# PCB-Switches.net
KiCad netlist of a schematic drawn in EAGLE
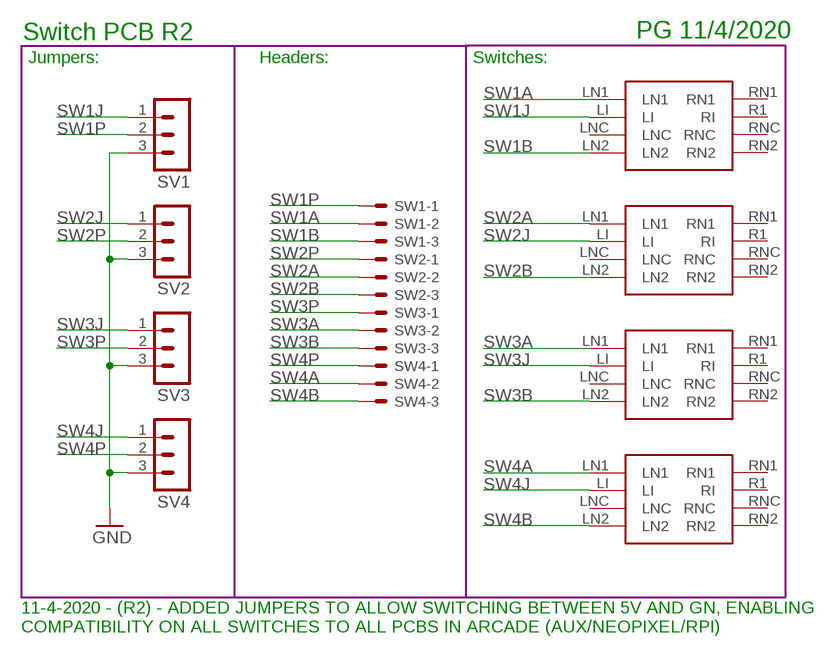
[diagram p0: schematic, sheet 1]

(export (version "E")
  (design (tool "Eeschema 10.0.6"))
  (components
    (comp (ref "SV1")
      (value "MA03-1")
      (footprint "eagle-import:MA03-1")
      (libsource (lib "eagle-import") (part "MA03-1"))
    )
    (comp (ref "SV2")
      (value "MA03-1")
      (footprint "eagle-import:MA03-1")
      (libsource (lib "eagle-import") (part "MA03-1"))
    )
    (comp (ref "SV3")
      (value "MA03-1")
      (footprint "eagle-import:MA03-1")
      (libsource (lib "eagle-import") (part "MA03-1"))
    )
    (comp (ref "SV4")
      (value "MA03-1")
      (footprint "eagle-import:MA03-1")
      (libsource (lib "eagle-import") (part "MA03-1"))
    )
    (comp (ref "SW1")
      (value "KK-156-3")
      (footprint "eagle-import:KK-156-3")
      (fields (field (name "MF") "MOLEX"))
      (libsource (lib "eagle-import") (part "KK-156-3"))
    )
    (comp (ref "SW2")
      (value "KK-156-3")
      (footprint "eagle-import:KK-156-3")
      (fields (field (name "MF") "MOLEX"))
      (libsource (lib "eagle-import") (part "KK-156-3"))
    )
    (comp (ref "SW3")
      (value "KK-156-3")
      (footprint "eagle-import:KK-156-3")
      (fields (field (name "MF") "MOLEX"))
      (libsource (lib "eagle-import") (part "KK-156-3"))
    )
    (comp (ref "SW4")
      (value "KK-156-3")
      (footprint "eagle-import:KK-156-3")
      (fields (field (name "MF") "MOLEX"))
      (libsource (lib "eagle-import") (part "KK-156-3"))
    )
    (comp (ref "U$1")
      (value "ARCADESWITCH")
      (footprint "eagle-import:ARCADESWITCH")
      (libsource (lib "eagle-import") (part "ARCADESWITCH"))
    )
    (comp (ref "U$2")
      (value "ARCADESWITCH")
      (footprint "eagle-import:ARCADESWITCH")
      (libsource (lib "eagle-import") (part "ARCADESWITCH"))
    )
    (comp (ref "U$3")
      (value "ARCADESWITCH")
      (footprint "eagle-import:ARCADESWITCH")
      (libsource (lib "eagle-import") (part "ARCADESWITCH"))
    )
    (comp (ref "U$4")
      (value "ARCADESWITCH")
      (footprint "eagle-import:ARCADESWITCH")
      (libsource (lib "eagle-import") (part "ARCADESWITCH"))
    )
  )
  (nets
    (net (code "1") (name "/SW1A") (class "Default")
      (node (ref "SW1") (pin "2") (pinfunction "S_2") (pintype "passive"))
      (node (ref "U$1") (pin "LN1") (pinfunction "LN1_LN1") (pintype "bidirectional"))
    )
    (net (code "2") (name "/SW1B") (class "Default")
      (node (ref "SW1") (pin "3") (pinfunction "S_3") (pintype "passive"))
      (node (ref "U$1") (pin "LN2") (pinfunction "LN2_LN2") (pintype "bidirectional"))
    )
    (net (code "3") (name "/SW1J") (class "Default")
      (node (ref "SV1") (pin "1") (pinfunction "1_1") (pintype "passive"))
      (node (ref "U$1") (pin "LI") (pinfunction "LI_LI") (pintype "bidirectional"))
    )
    (net (code "4") (name "/SW1P") (class "Default")
      (node (ref "SV1") (pin "2") (pinfunction "2_2") (pintype "passive"))
      (node (ref "SW1") (pin "1") (pinfunction "S_1") (pintype "passive"))
    )
    (net (code "5") (name "/SW2A") (class "Default")
      (node (ref "SW2") (pin "2") (pinfunction "S_2") (pintype "passive"))
      (node (ref "U$2") (pin "LN1") (pinfunction "LN1_LN1") (pintype "bidirectional"))
    )
    (net (code "6") (name "/SW2B") (class "Default")
      (node (ref "SW2") (pin "3") (pinfunction "S_3") (pintype "passive"))
      (node (ref "U$2") (pin "LN2") (pinfunction "LN2_LN2") (pintype "bidirectional"))
    )
    (net (code "7") (name "/SW2J") (class "Default")
      (node (ref "SV2") (pin "1") (pinfunction "1_1") (pintype "passive"))
      (node (ref "U$2") (pin "LI") (pinfunction "LI_LI") (pintype "bidirectional"))
    )
    (net (code "8") (name "/SW2P") (class "Default")
      (node (ref "SV2") (pin "2") (pinfunction "2_2") (pintype "passive"))
      (node (ref "SW2") (pin "1") (pinfunction "S_1") (pintype "passive"))
    )
    (net (code "9") (name "/SW3A") (class "Default")
      (node (ref "SW3") (pin "2") (pinfunction "S_2") (pintype "passive"))
      (node (ref "U$3") (pin "LN1") (pinfunction "LN1_LN1") (pintype "bidirectional"))
    )
    (net (code "10") (name "/SW3B") (class "Default")
      (node (ref "SW3") (pin "3") (pinfunction "S_3") (pintype "passive"))
      (node (ref "U$3") (pin "LN2") (pinfunction "LN2_LN2") (pintype "bidirectional"))
    )
    (net (code "11") (name "/SW3J") (class "Default")
      (node (ref "SV3") (pin "1") (pinfunction "1_1") (pintype "passive"))
      (node (ref "U$3") (pin "LI") (pinfunction "LI_LI") (pintype "bidirectional"))
    )
    (net (code "12") (name "/SW3P") (class "Default")
      (node (ref "SV3") (pin "2") (pinfunction "2_2") (pintype "passive"))
      (node (ref "SW3") (pin "1") (pinfunction "S_1") (pintype "passive"))
    )
    (net (code "13") (name "/SW4A") (class "Default")
      (node (ref "SW4") (pin "2") (pinfunction "S_2") (pintype "passive"))
      (node (ref "U$4") (pin "LN1") (pinfunction "LN1_LN1") (pintype "bidirectional"))
    )
    (net (code "14") (name "/SW4B") (class "Default")
      (node (ref "SW4") (pin "3") (pinfunction "S_3") (pintype "passive"))
      (node (ref "U$4") (pin "LN2") (pinfunction "LN2_LN2") (pintype "bidirectional"))
    )
    (net (code "15") (name "/SW4J") (class "Default")
      (node (ref "SV4") (pin "1") (pinfunction "1_1") (pintype "passive"))
      (node (ref "U$4") (pin "LI") (pinfunction "LI_LI") (pintype "bidirectional"))
    )
    (net (code "16") (name "/SW4P") (class "Default")
      (node (ref "SV4") (pin "2") (pinfunction "2_2") (pintype "passive"))
      (node (ref "SW4") (pin "1") (pinfunction "S_1") (pintype "passive"))
    )
    (net (code "17") (name "GND") (class "Default")
      (node (ref "SV1") (pin "3") (pinfunction "3_3") (pintype "passive"))
      (node (ref "SV2") (pin "3") (pinfunction "3_3") (pintype "passive"))
      (node (ref "SV3") (pin "3") (pinfunction "3_3") (pintype "passive"))
      (node (ref "SV4") (pin "3") (pinfunction "3_3") (pintype "passive"))
    )
    (net (code "18") (name "unconnected-(U$1-PadLNC)") (class "Default")
      (node (ref "U$1") (pin "LNC") (pinfunction "LNC_LNC") (pintype "bidirectional"))
    )
    (net (code "19") (name "unconnected-(U$1-PadRN1)") (class "Default")
      (node (ref "U$1") (pin "RN1") (pinfunction "RN1_RN1") (pintype "bidirectional"))
    )
    (net (code "20") (name "unconnected-(U$1-PadRN2)") (class "Default")
      (node (ref "U$1") (pin "RN2") (pinfunction "RN2_RN2") (pintype "bidirectional"))
    )
    (net (code "21") (name "unconnected-(U$1-PadRNC)") (class "Default")
      (node (ref "U$1") (pin "RNC") (pinfunction "RNC_RNC") (pintype "bidirectional"))
    )
    (net (code "22") (name "unconnected-(U$1-RI-PadR1)") (class "Default")
      (node (ref "U$1") (pin "R1") (pinfunction "RI_R1") (pintype "bidirectional"))
    )
    (net (code "23") (name "unconnected-(U$2-PadLNC)") (class "Default")
      (node (ref "U$2") (pin "LNC") (pinfunction "LNC_LNC") (pintype "bidirectional"))
    )
    (net (code "24") (name "unconnected-(U$2-PadRN1)") (class "Default")
      (node (ref "U$2") (pin "RN1") (pinfunction "RN1_RN1") (pintype "bidirectional"))
    )
    (net (code "25") (name "unconnected-(U$2-PadRN2)") (class "Default")
      (node (ref "U$2") (pin "RN2") (pinfunction "RN2_RN2") (pintype "bidirectional"))
    )
    (net (code "26") (name "unconnected-(U$2-PadRNC)") (class "Default")
      (node (ref "U$2") (pin "RNC") (pinfunction "RNC_RNC") (pintype "bidirectional"))
    )
    (net (code "27") (name "unconnected-(U$2-RI-PadR1)") (class "Default")
      (node (ref "U$2") (pin "R1") (pinfunction "RI_R1") (pintype "bidirectional"))
    )
    (net (code "28") (name "unconnected-(U$3-PadLNC)") (class "Default")
      (node (ref "U$3") (pin "LNC") (pinfunction "LNC_LNC") (pintype "bidirectional"))
    )
    (net (code "29") (name "unconnected-(U$3-PadRN1)") (class "Default")
      (node (ref "U$3") (pin "RN1") (pinfunction "RN1_RN1") (pintype "bidirectional"))
    )
    (net (code "30") (name "unconnected-(U$3-PadRN2)") (class "Default")
      (node (ref "U$3") (pin "RN2") (pinfunction "RN2_RN2") (pintype "bidirectional"))
    )
    (net (code "31") (name "unconnected-(U$3-PadRNC)") (class "Default")
      (node (ref "U$3") (pin "RNC") (pinfunction "RNC_RNC") (pintype "bidirectional"))
    )
    (net (code "32") (name "unconnected-(U$3-RI-PadR1)") (class "Default")
      (node (ref "U$3") (pin "R1") (pinfunction "RI_R1") (pintype "bidirectional"))
    )
    (net (code "33") (name "unconnected-(U$4-PadLNC)") (class "Default")
      (node (ref "U$4") (pin "LNC") (pinfunction "LNC_LNC") (pintype "bidirectional"))
    )
    (net (code "34") (name "unconnected-(U$4-PadRN1)") (class "Default")
      (node (ref "U$4") (pin "RN1") (pinfunction "RN1_RN1") (pintype "bidirectional"))
    )
    (net (code "35") (name "unconnected-(U$4-PadRN2)") (class "Default")
      (node (ref "U$4") (pin "RN2") (pinfunction "RN2_RN2") (pintype "bidirectional"))
    )
    (net (code "36") (name "unconnected-(U$4-PadRNC)") (class "Default")
      (node (ref "U$4") (pin "RNC") (pinfunction "RNC_RNC") (pintype "bidirectional"))
    )
    (net (code "37") (name "unconnected-(U$4-RI-PadR1)") (class "Default")
      (node (ref "U$4") (pin "R1") (pinfunction "RI_R1") (pintype "bidirectional"))
    )
  )
)
